# FuelGauge_Sheet.net
KiCad netlist of a schematic drawn in Altium Designer
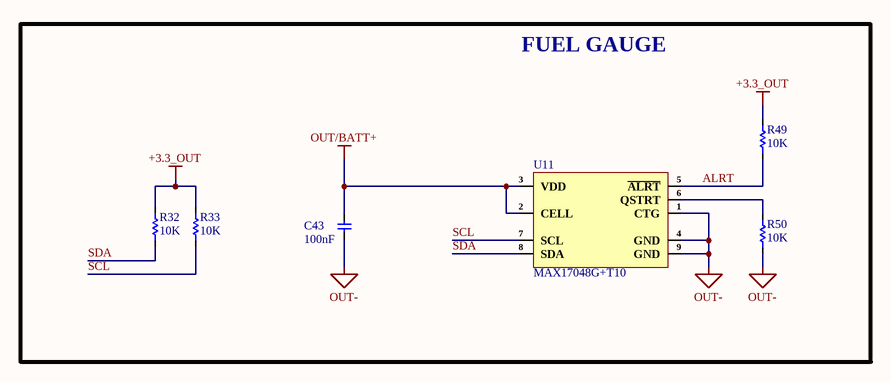
[diagram p0: FuelGauge_Sheet.SchDoc]

(export (version "E")
  (design (tool "Eeschema 10.0.6"))
  (components
    (comp (ref "C43")
      (value "100nF")
      (footprint "cap-0402")
      (description "CAP CER 0.1UF 50V X7R 0402")
      (fields
        (field (name "MANUFACTURER") "TDK")
        (field (name "MANUFACTURER PART NUMBER") "C1005X7R1H104KT000F")
      )
      (libsource (lib "eSpark Libraries") (part "C1005X7R1H104KT000F"))
    )
    (comp (ref "R32")
      (value "10K")
      (footprint "Res-0402")
      (description "RES 10K OHM 1% 1/16W 0402")
      (fields
        (field (name "MANUFACTURER") "Yageo")
        (field (name "MANUFACTURER PART NUMBER") "RC0402FR-0710KL")
      )
      (libsource (lib "eSpark Libraries") (part "RC0402FR-0710KL"))
    )
    (comp (ref "R33")
      (value "10K")
      (footprint "Res-0402")
      (description "RES 10K OHM 1% 1/16W 0402")
      (fields
        (field (name "MANUFACTURER") "Yageo")
        (field (name "MANUFACTURER PART NUMBER") "RC0402FR-0710KL")
      )
      (libsource (lib "eSpark Libraries") (part "RC0402FR-0710KL"))
    )
    (comp (ref "R49")
      (value "10K")
      (footprint "Res-0402")
      (description "RES 10K OHM 1% 1/16W 0402")
      (fields
        (field (name "MANUFACTURER") "Yageo")
        (field (name "MANUFACTURER PART NUMBER") "RC0402FR-0710KL")
      )
      (libsource (lib "eSpark Libraries") (part "RC0402FR-0710KL"))
    )
    (comp (ref "R50")
      (value "10K")
      (footprint "Res-0402")
      (description "RES 10K OHM 1% 1/16W 0402")
      (fields
        (field (name "MANUFACTURER") "Yageo")
        (field (name "MANUFACTURER PART NUMBER") "RC0402FR-0710KL")
      )
      (libsource (lib "eSpark Libraries") (part "RC0402FR-0710KL"))
    )
    (comp (ref "U11")
      (value "MAX17048G+T10")
      (footprint "8-TDFN-EP (2x2)")
      (description "IC BATT MON LI-ION 1CELL 8TDFN")
      (fields (field (name "MANUFACTURER") "Maxim") (field (name "LCSC PART NUMBER") "C2682616"))
      (libsource (lib "eSpark Libraries") (part "MAX17048G+T10"))
    )
  )
  (nets
    (net (code "1") (name "+3.3_OUT") (class "Default")
      (node (ref "R32") (pin "2") (pinfunction "2_2") (pintype "passive"))
      (node (ref "R33") (pin "2") (pinfunction "2_2") (pintype "passive"))
      (node (ref "R49") (pin "2") (pinfunction "2_2") (pintype "passive"))
    )
    (net (code "2") (name "/ALRT") (class "Default")
      (node (ref "R49") (pin "1") (pinfunction "1_1") (pintype "passive"))
      (node (ref "U11") (pin "5") (pinfunction "~{ALRT}_5") (pintype "passive"))
    )
    (net (code "3") (name "/SCL") (class "Default")
      (node (ref "R33") (pin "1") (pinfunction "1_1") (pintype "passive"))
      (node (ref "U11") (pin "7") (pinfunction "SCL_7") (pintype "passive"))
    )
    (net (code "4") (name "/SDA") (class "Default")
      (node (ref "R32") (pin "1") (pinfunction "1_1") (pintype "passive"))
      (node (ref "U11") (pin "8") (pinfunction "SDA_8") (pintype "passive"))
    )
    (net (code "5") (name "Net-(U11-QSTRT)") (class "Default")
      (node (ref "R50") (pin "2") (pinfunction "2_2") (pintype "passive"))
      (node (ref "U11") (pin "6") (pinfunction "QSTRT_6") (pintype "passive"))
    )
    (net (code "6") (name "OUT-") (class "Default")
      (node (ref "C43") (pin "2") (pinfunction "2_2") (pintype "passive"))
      (node (ref "R50") (pin "1") (pinfunction "1_1") (pintype "passive"))
      (node (ref "U11") (pin "1") (pinfunction "CTG_1") (pintype "passive"))
      (node (ref "U11") (pin "4") (pinfunction "GND_4") (pintype "passive"))
      (node (ref "U11") (pin "9") (pinfunction "GND_9") (pintype "passive"))
    )
    (net (code "7") (name "OUT{slash}BATT+") (class "Default")
      (node (ref "C43") (pin "1") (pinfunction "1_1") (pintype "passive"))
      (node (ref "U11") (pin "2") (pinfunction "CELL_2") (pintype "passive"))
      (node (ref "U11") (pin "3") (pinfunction "VDD_3") (pintype "passive"))
    )
  )
)
